# MOASCT.net
KiCad netlist of a schematic drawn in Altium Designer
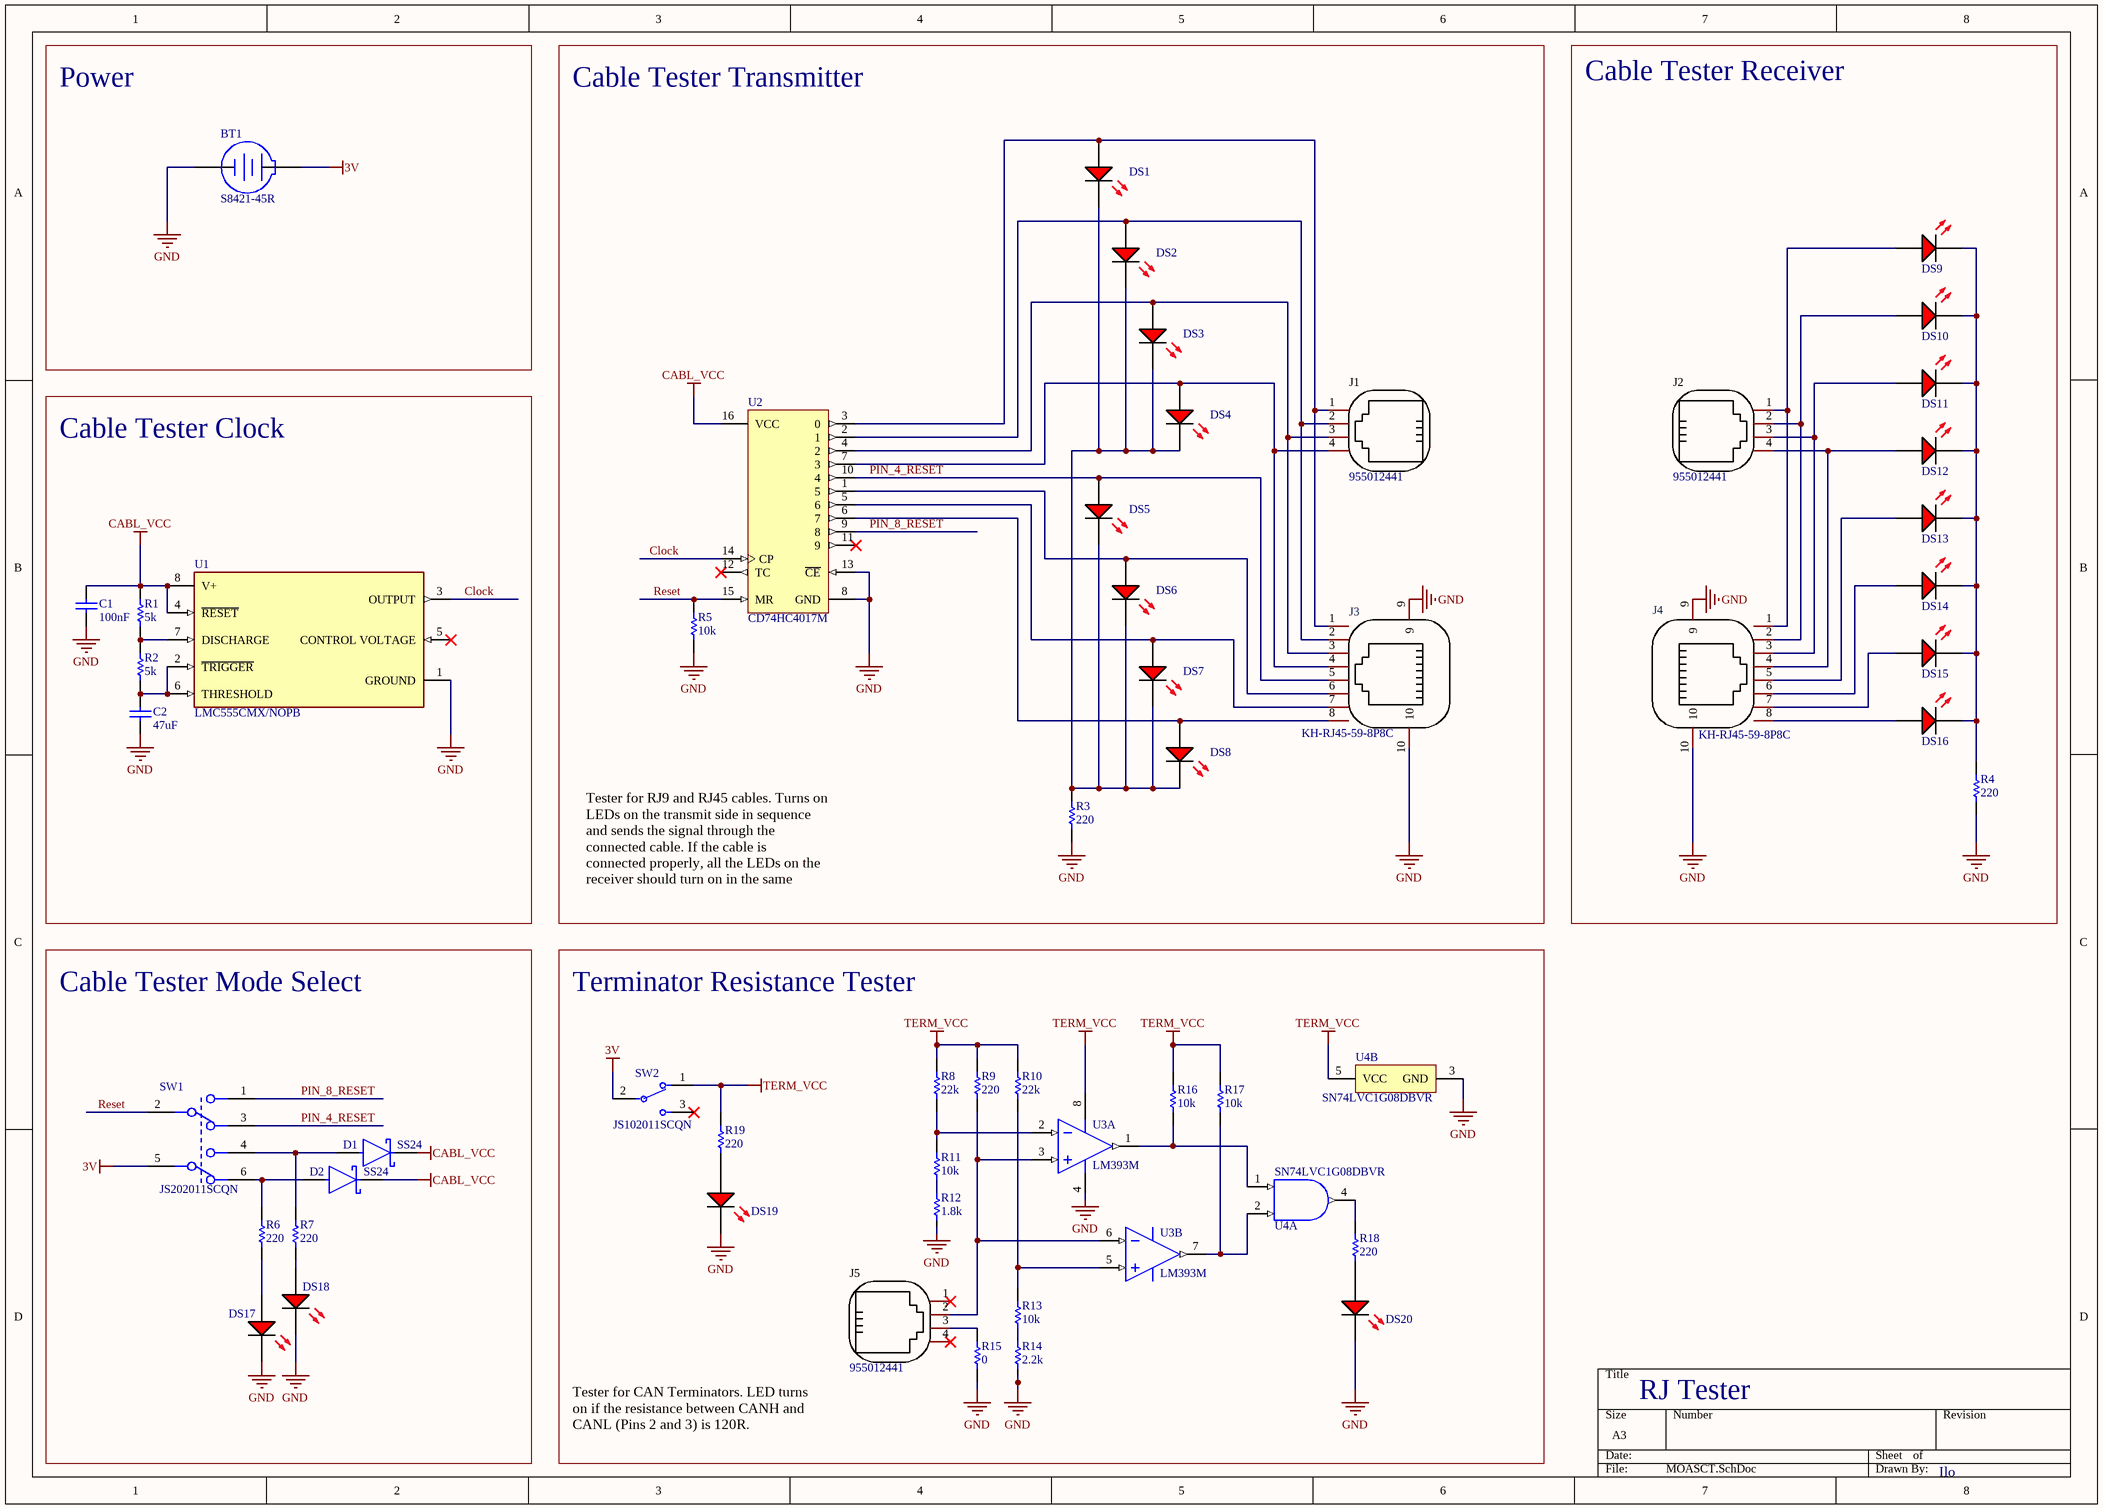
[diagram p0: MOASCT.SchDoc]

(export (version "E")
  (design (tool "Eeschema 10.0.6"))
  (components
    (comp (ref "BT1")
      (value "S8421-45R")
      (footprint "HRWN-S8421-45R_V")
      (description "Bettery Coin Cell Holder, Suitable for CR2032, -40 to 105 degC, 2-Pin SMD, RoHS, Tape and Reel")
      (fields (field (name "MANUFACTURER") "Harwin"))
      (libsource (lib "Altium Content Vault") (part "BATTERY-HOLDER-COIN-2"))
    )
    (comp (ref "C1")
      (value "100nF")
      (footprint "CAPC1608X92X38ML15T08")
      (fields (field (name "MANUFACTURER") "Vitramon") (field (name "PART NUMBER") "VJ0603Y103KXAAC"))
      (libsource (lib "Altium Content Vault") (part "CAP"))
    )
    (comp (ref "C2")
      (value "47uF")
      (footprint "CAPC2013X145X48NL20T23")
      (fields (field (name "PART NUMBER") "VJ0805Y104KXAAT") (field (name "MANUFACTURER") "Vitramon"))
      (libsource (lib "Altium Content Vault") (part "CAP"))
    )
    (comp (ref "D1")
      (value "SS24")
      (footprint "FP-95401-MFG")
      (description "SS24-E3/5BT Rectifier Diode, Schottky, 1 Phase, 1 Element, 2A, 40V V(RRM), Silicon, DO-214AA")
      (libsource (lib "Altium Content Vault") (part "c1678fac7984e62e0809fbf79c06691"))
    )
    (comp (ref "D2")
      (value "SS24")
      (footprint "FP-95401-MFG")
      (description "SS24-E3/5BT Rectifier Diode, Schottky, 1 Phase, 1 Element, 2A, 40V V(RRM), Silicon, DO-214AA")
      (libsource (lib "Altium Content Vault") (part "c1678fac7984e62e0809fbf79c06691"))
    )
    (comp (ref "DS1")
      (value "SML-LXT0805IW-TR")
      (footprint "LUMX-SML-LXT0805_V")
      (description "LED, RED, 635 nm, 2 V, -25 to 80 degC, 2-Pin SMD, RoHS, Tape and Reel")
      (libsource (lib "Altium Content Vault") (part "LED-RED-AK-2"))
    )
    (comp (ref "DS2")
      (value "SML-LXT0805IW-TR")
      (footprint "LUMX-SML-LXT0805_V")
      (description "LED, RED, 635 nm, 2 V, -25 to 80 degC, 2-Pin SMD, RoHS, Tape and Reel")
      (libsource (lib "Altium Content Vault") (part "LED-RED-AK-2"))
    )
    (comp (ref "DS3")
      (value "SML-LXT0805IW-TR")
      (footprint "LUMX-SML-LXT0805_V")
      (description "LED, RED, 635 nm, 2 V, -25 to 80 degC, 2-Pin SMD, RoHS, Tape and Reel")
      (libsource (lib "Altium Content Vault") (part "LED-RED-AK-2"))
    )
    (comp (ref "DS4")
      (value "SML-LXT0805IW-TR")
      (footprint "LUMX-SML-LXT0805_V")
      (description "LED, RED, 635 nm, 2 V, -25 to 80 degC, 2-Pin SMD, RoHS, Tape and Reel")
      (libsource (lib "Altium Content Vault") (part "LED-RED-AK-2"))
    )
    (comp (ref "DS5")
      (value "SML-LXT0805IW-TR")
      (footprint "LUMX-SML-LXT0805_V")
      (description "LED, RED, 635 nm, 2 V, -25 to 80 degC, 2-Pin SMD, RoHS, Tape and Reel")
      (libsource (lib "Altium Content Vault") (part "LED-RED-AK-2"))
    )
    (comp (ref "DS6")
      (value "SML-LXT0805IW-TR")
      (footprint "LUMX-SML-LXT0805_V")
      (description "LED, RED, 635 nm, 2 V, -25 to 80 degC, 2-Pin SMD, RoHS, Tape and Reel")
      (libsource (lib "Altium Content Vault") (part "LED-RED-AK-2"))
    )
    (comp (ref "DS7")
      (value "SML-LXT0805IW-TR")
      (footprint "LUMX-SML-LXT0805_V")
      (description "LED, RED, 635 nm, 2 V, -25 to 80 degC, 2-Pin SMD, RoHS, Tape and Reel")
      (libsource (lib "Altium Content Vault") (part "LED-RED-AK-2"))
    )
    (comp (ref "DS8")
      (value "SML-LXT0805IW-TR")
      (footprint "LUMX-SML-LXT0805_V")
      (description "LED, RED, 635 nm, 2 V, -25 to 80 degC, 2-Pin SMD, RoHS, Tape and Reel")
      (libsource (lib "Altium Content Vault") (part "LED-RED-AK-2"))
    )
    (comp (ref "DS9")
      (value "SML-LXT0805IW-TR")
      (footprint "LUMX-SML-LXT0805_V")
      (description "LED, RED, 635 nm, 2 V, -25 to 80 degC, 2-Pin SMD, RoHS, Tape and Reel")
      (libsource (lib "Altium Content Vault") (part "LED-RED-AK-2"))
    )
    (comp (ref "DS10")
      (value "SML-LXT0805IW-TR")
      (footprint "LUMX-SML-LXT0805_V")
      (description "LED, RED, 635 nm, 2 V, -25 to 80 degC, 2-Pin SMD, RoHS, Tape and Reel")
      (libsource (lib "Altium Content Vault") (part "LED-RED-AK-2"))
    )
    (comp (ref "DS11")
      (value "SML-LXT0805IW-TR")
      (footprint "LUMX-SML-LXT0805_V")
      (description "LED, RED, 635 nm, 2 V, -25 to 80 degC, 2-Pin SMD, RoHS, Tape and Reel")
      (libsource (lib "Altium Content Vault") (part "LED-RED-AK-2"))
    )
    (comp (ref "DS12")
      (value "SML-LXT0805IW-TR")
      (footprint "LUMX-SML-LXT0805_V")
      (description "LED, RED, 635 nm, 2 V, -25 to 80 degC, 2-Pin SMD, RoHS, Tape and Reel")
      (libsource (lib "Altium Content Vault") (part "LED-RED-AK-2"))
    )
    (comp (ref "DS13")
      (value "SML-LXT0805IW-TR")
      (footprint "LUMX-SML-LXT0805_V")
      (description "LED, RED, 635 nm, 2 V, -25 to 80 degC, 2-Pin SMD, RoHS, Tape and Reel")
      (libsource (lib "Altium Content Vault") (part "LED-RED-AK-2"))
    )
    (comp (ref "DS14")
      (value "SML-LXT0805IW-TR")
      (footprint "LUMX-SML-LXT0805_V")
      (description "LED, RED, 635 nm, 2 V, -25 to 80 degC, 2-Pin SMD, RoHS, Tape and Reel")
      (libsource (lib "Altium Content Vault") (part "LED-RED-AK-2"))
    )
    (comp (ref "DS15")
      (value "SML-LXT0805IW-TR")
      (footprint "LUMX-SML-LXT0805_V")
      (description "LED, RED, 635 nm, 2 V, -25 to 80 degC, 2-Pin SMD, RoHS, Tape and Reel")
      (libsource (lib "Altium Content Vault") (part "LED-RED-AK-2"))
    )
    (comp (ref "DS16")
      (value "SML-LXT0805IW-TR")
      (footprint "LUMX-SML-LXT0805_V")
      (description "LED, RED, 635 nm, 2 V, -25 to 80 degC, 2-Pin SMD, RoHS, Tape and Reel")
      (libsource (lib "Altium Content Vault") (part "LED-RED-AK-2"))
    )
    (comp (ref "DS17")
      (value "SML-LXT0805IW-TR")
      (footprint "LUMX-SML-LXT0805_V")
      (description "LED, RED, 635 nm, 2 V, -25 to 80 degC, 2-Pin SMD, RoHS, Tape and Reel")
      (libsource (lib "Altium Content Vault") (part "LED-RED-AK-2"))
    )
    (comp (ref "DS18")
      (value "SML-LXT0805IW-TR")
      (footprint "LUMX-SML-LXT0805_V")
      (description "LED, RED, 635 nm, 2 V, -25 to 80 degC, 2-Pin SMD, RoHS, Tape and Reel")
      (libsource (lib "Altium Content Vault") (part "LED-RED-AK-2"))
    )
    (comp (ref "DS19")
      (value "SML-LXT0805IW-TR")
      (footprint "LUMX-SML-LXT0805_V")
      (description "LED, RED, 635 nm, 2 V, -25 to 80 degC, 2-Pin SMD, RoHS, Tape and Reel")
      (libsource (lib "Altium Content Vault") (part "LED-RED-AK-2"))
    )
    (comp (ref "DS20")
      (value "SML-LXT0805IW-TR")
      (footprint "LUMX-SML-LXT0805_V")
      (description "LED, RED, 635 nm, 2 V, -25 to 80 degC, 2-Pin SMD, RoHS, Tape and Reel")
      (libsource (lib "Altium Content Vault") (part "LED-RED-AK-2"))
    )
    (comp (ref "J1")
      (value "955012441")
      (footprint "RJ45-TH_95501-2441:RJ45-TH_95501-2441")
      (fields (field (name "MANUFACTURER") "MOLEX"))
      (libsource (lib "9550124411_955012441.schdoc") (part "955012441"))
    )
    (comp (ref "J2")
      (value "955012441")
      (footprint "RJ45-TH_95501-2441:RJ45-TH_95501-2441")
      (fields (field (name "MANUFACTURER") "MOLEX"))
      (libsource (lib "9550124411_955012441.schdoc") (part "955012441"))
    )
    (comp (ref "J3")
      (value "KH-RJ45-59-8P8C")
      (footprint "RJ45-TH_KINGHELM_KH-RJ45-59-8P8C:RJ45-TH_KINGHELM_KH-RJ45-59-8P8C")
      (fields (field (name "MANUFACTURER") "kinghelm(金航标)"))
      (libsource (lib "KH-RJ45-59-8P8C1_KH-RJ45-59-8P8C") (part "KH-RJ45-59-8P8C"))
    )
    (comp (ref "J4")
      (value "KH-RJ45-59-8P8C")
      (footprint "RJ45-TH_KINGHELM_KH-RJ45-59-8P8C:RJ45-TH_KINGHELM_KH-RJ45-59-8P8C")
      (fields (field (name "MANUFACTURER") "kinghelm(金航标)"))
      (libsource (lib "KH-RJ45-59-8P8C1_KH-RJ45-59-8P8C") (part "KH-RJ45-59-8P8C"))
    )
    (comp (ref "J5")
      (value "955012441")
      (footprint "RJ45-TH_95501-2441:RJ45-TH_95501-2441")
      (fields (field (name "MANUFACTURER") "MOLEX"))
      (libsource (lib "9550124411_955012441.schdoc") (part "955012441"))
    )
    (comp (ref "R1")
      (value "5k")
      (footprint "RESC1609X50X30ML10T20")
      (fields (field (name "PART NUMBER") "CRCW060315K0FKEA") (field (name "MANUFACTURER") "Vishay Dale"))
      (libsource (lib "Altium Content Vault") (part "RES"))
    )
    (comp (ref "R2")
      (value "5k")
      (footprint "RESC1609X50X30ML10T20")
      (fields (field (name "PART NUMBER") "CRCW060315K0FKEA") (field (name "MANUFACTURER") "Vishay Dale"))
      (libsource (lib "Altium Content Vault") (part "RES"))
    )
    (comp (ref "R3")
      (value "220")
      (footprint "RESC1609X50X30ML10T20")
      (fields (field (name "PART NUMBER") "CRCW060315K0FKEA") (field (name "MANUFACTURER") "Vishay Dale"))
      (libsource (lib "Altium Content Vault") (part "RES"))
    )
    (comp (ref "R4")
      (value "220")
      (footprint "RESC1609X50X30ML10T20")
      (fields (field (name "PART NUMBER") "CRCW060315K0FKEA") (field (name "MANUFACTURER") "Vishay Dale"))
      (libsource (lib "Altium Content Vault") (part "RES"))
    )
    (comp (ref "R5")
      (value "10k")
      (footprint "RESC1609X50X30ML10T20")
      (fields (field (name "PART NUMBER") "CRCW060315K0FKEA") (field (name "MANUFACTURER") "Vishay Dale"))
      (libsource (lib "Altium Content Vault") (part "RES"))
    )
    (comp (ref "R6")
      (value "220")
      (footprint "RESC1609X50X30ML10T20")
      (fields (field (name "PART NUMBER") "CRCW060315K0FKEA") (field (name "MANUFACTURER") "Vishay Dale"))
      (libsource (lib "Altium Content Vault") (part "RES"))
    )
    (comp (ref "R7")
      (value "220")
      (footprint "RESC1609X50X30ML10T20")
      (fields (field (name "PART NUMBER") "CRCW060315K0FKEA") (field (name "MANUFACTURER") "Vishay Dale"))
      (libsource (lib "Altium Content Vault") (part "RES"))
    )
    (comp (ref "R8")
      (value "22k")
      (footprint "RESC1609X50X30ML10T20")
      (fields (field (name "PART NUMBER") "CRCW060315K0FKEA") (field (name "MANUFACTURER") "Vishay Dale"))
      (libsource (lib "Altium Content Vault") (part "RES"))
    )
    (comp (ref "R9")
      (value "220")
      (footprint "RESC1609X50X30ML10T20")
      (fields (field (name "PART NUMBER") "CRCW060315K0FKEA") (field (name "MANUFACTURER") "Vishay Dale"))
      (libsource (lib "Altium Content Vault") (part "RES"))
    )
    (comp (ref "R10")
      (value "22k")
      (footprint "RESC1609X50X30ML10T20")
      (fields (field (name "PART NUMBER") "CRCW060315K0FKEA") (field (name "MANUFACTURER") "Vishay Dale"))
      (libsource (lib "Altium Content Vault") (part "RES"))
    )
    (comp (ref "R11")
      (value "10k")
      (footprint "RESC1609X50X30ML10T20")
      (fields (field (name "PART NUMBER") "CRCW060315K0FKEA") (field (name "MANUFACTURER") "Vishay Dale"))
      (libsource (lib "Altium Content Vault") (part "RES"))
    )
    (comp (ref "R12")
      (value "1.8k")
      (footprint "RESC1609X50X30ML10T20")
      (fields (field (name "PART NUMBER") "CRCW060315K0FKEA") (field (name "MANUFACTURER") "Vishay Dale"))
      (libsource (lib "Altium Content Vault") (part "RES"))
    )
    (comp (ref "R13")
      (value "10k")
      (footprint "RESC1609X50X30ML10T20")
      (fields (field (name "PART NUMBER") "CRCW060315K0FKEA") (field (name "MANUFACTURER") "Vishay Dale"))
      (libsource (lib "Altium Content Vault") (part "RES"))
    )
    (comp (ref "R14")
      (value "2.2k")
      (footprint "RESC1609X50X30ML10T20")
      (fields (field (name "PART NUMBER") "CRCW060315K0FKEA") (field (name "MANUFACTURER") "Vishay Dale"))
      (libsource (lib "Altium Content Vault") (part "RES"))
    )
    (comp (ref "R15")
      (value "0")
      (footprint "RESC1609X50X30ML10T20")
      (fields (field (name "PART NUMBER") "CRCW060315K0FKEA") (field (name "MANUFACTURER") "Vishay Dale"))
      (libsource (lib "Altium Content Vault") (part "RES"))
    )
    (comp (ref "R16")
      (value "10k")
      (footprint "RESC1609X50X30ML10T20")
      (fields (field (name "PART NUMBER") "CRCW060315K0FKEA") (field (name "MANUFACTURER") "Vishay Dale"))
      (libsource (lib "Altium Content Vault") (part "RES"))
    )
    (comp (ref "R17")
      (value "10k")
      (footprint "RESC1609X50X30ML10T20")
      (fields (field (name "PART NUMBER") "CRCW060315K0FKEA") (field (name "MANUFACTURER") "Vishay Dale"))
      (libsource (lib "Altium Content Vault") (part "RES"))
    )
    (comp (ref "R18")
      (value "220")
      (footprint "RESC1609X50X30ML10T20")
      (fields (field (name "PART NUMBER") "CRCW060315K0FKEA") (field (name "MANUFACTURER") "Vishay Dale"))
      (libsource (lib "Altium Content Vault") (part "RES"))
    )
    (comp (ref "R19")
      (value "220")
      (footprint "RESC1609X50X30ML10T20")
      (fields (field (name "PART NUMBER") "CRCW060315K0FKEA") (field (name "MANUFACTURER") "Vishay Dale"))
      (libsource (lib "Altium Content Vault") (part "RES"))
    )
    (comp (ref "SW1")
      (value "JS202011SCQN")
      (footprint "FP-JS202011SCQN-MFG")
      (description "SWITCH SLIDE DPDT 300MA 6V")
      (libsource (lib "Altium Content Vault") (part "ac99ea1af431c19115f5225061c5c88"))
    )
    (comp (ref "SW2")
      (value "JS102011SCQN")
      (footprint "FP-JS102011SCQN-MFG")
      (description "SWITCH SLIDE SPDT 300MA 6V")
      (libsource (lib "Altium Content Vault") (part "39e195cbbadc85d1df0d7eb6847d379"))
    )
    (comp (ref "U1")
      (value "LMC555CMX/NOPB")
      (footprint "FP-D0008A-MFG")
      (description "IC OSC SINGLE TIMER 3MHZ 8-SOIC")
      (fields
        (field (name "OCTOPART") "https://octopart.com/lmc555cmx%2Fnopb-texas+instruments-24815227")
        (field (name "MANUFACTURER") "Texas Instruments")
      )
      (libsource (lib "Altium Content Vault") (part "2d4910f0af3888ed72da4973d42bf58"))
    )
    (comp (ref "U2")
      (value "CD74HC4017M")
      (footprint "D0016A_N")
      (description "High Speed CMOS Logic Decade Counter/Divider with 10 Decoded Outputs, D0016A, TUBE")
      (fields
        (field (name "MANUFACTURER") "Texas Instruments")
        (field (name "GENERIC PART NUMBER") "CD74HC4017")
      )
      (libsource (lib "Altium Content Vault") (part "TI-CD74HC4017-16"))
    )
    (comp (ref "U3")
      (value "LM393M")
      (footprint "D0008A_L")
      (description "Low Power Low Offset Voltage Dual Comparator, 8-pin Narrow SOIC")
      (fields (field (name "MANUFACTURER") "Texas Instruments"))
      (libsource (lib "Altium Content Vault") (part "AN-COMP-LM193-8"))
    )
    (comp (ref "U4")
      (value "SN74LVC1G08DBVR")
      (footprint "DBV0005A_M")
      (description "Single 2-Input Positive-AND Gate, DBV0005A, LARGE T&R")
      (fields
        (field (name "GENERIC PART NUMBER") "SN74LVC1G08")
        (field (name "MANUFACTURER") "Texas Instruments")
      )
      (libsource (lib "Altium Content Vault") (part "TI-SN74XXX1X08-5"))
    )
  )
  (nets
    (net (code "1") (name "/Clock") (class "Default")
      (node (ref "U1") (pin "3") (pinfunction "OUTPUT_3") (pintype "output"))
      (node (ref "U2") (pin "14") (pinfunction "CP_14") (pintype "input"))
    )
    (net (code "2") (name "/PIN_4_RESET") (class "Default")
      (node (ref "DS5") (pin "1") (pinfunction "A_1") (pintype "passive"))
      (node (ref "J3") (pin "5") (pinfunction "5_5") (pintype "passive"))
      (node (ref "SW1") (pin "3") (pinfunction "3_3") (pintype "passive"))
      (node (ref "U2") (pin "10") (pinfunction "4_10") (pintype "output"))
    )
    (net (code "3") (name "/PIN_8_RESET") (class "Default")
      (node (ref "SW1") (pin "1") (pinfunction "1_1") (pintype "passive"))
      (node (ref "U2") (pin "9") (pinfunction "8_9") (pintype "output"))
    )
    (net (code "4") (name "/Reset") (class "Default")
      (node (ref "R5") (pin "2") (pinfunction "2_2") (pintype "passive"))
      (node (ref "SW1") (pin "2") (pinfunction "2_2") (pintype "passive"))
      (node (ref "U2") (pin "15") (pinfunction "MR_15") (pintype "input"))
    )
    (net (code "5") (name "3V") (class "Default")
      (node (ref "BT1") (pin "1") (pinfunction "+_1") (pintype "passive"))
      (node (ref "SW1") (pin "5") (pinfunction "5_5") (pintype "passive"))
      (node (ref "SW2") (pin "2") (pinfunction "C_2") (pintype "passive"))
    )
    (net (code "6") (name "CABL_VCC") (class "Default")
      (node (ref "C1") (pin "2") (pinfunction "2_2") (pintype "passive"))
      (node (ref "D1") (pin "1") (pinfunction "C_1") (pintype "passive"))
      (node (ref "D2") (pin "1") (pinfunction "C_1") (pintype "passive"))
      (node (ref "R1") (pin "2") (pinfunction "2_2") (pintype "passive"))
      (node (ref "U1") (pin "4") (pinfunction "~{RESET}_4") (pintype "input"))
      (node (ref "U1") (pin "8") (pinfunction "V+_8") (pintype "power_in"))
      (node (ref "U2") (pin "16") (pinfunction "VCC_16") (pintype "power_in"))
    )
    (net (code "7") (name "GND") (class "Default")
      (node (ref "BT1") (pin "2") (pinfunction "-_2") (pintype "passive"))
      (node (ref "C1") (pin "1") (pinfunction "1_1") (pintype "passive"))
      (node (ref "C2") (pin "2") (pinfunction "2_2") (pintype "passive"))
      (node (ref "DS17") (pin "2") (pinfunction "K_2") (pintype "passive"))
      (node (ref "DS18") (pin "2") (pinfunction "K_2") (pintype "passive"))
      (node (ref "DS19") (pin "2") (pinfunction "K_2") (pintype "passive"))
      (node (ref "DS20") (pin "2") (pinfunction "K_2") (pintype "passive"))
      (node (ref "J3") (pin "10") (pinfunction "10_10") (pintype "passive"))
      (node (ref "J3") (pin "9") (pinfunction "9_9") (pintype "passive"))
      (node (ref "J4") (pin "10") (pinfunction "10_10") (pintype "passive"))
      (node (ref "J4") (pin "9") (pinfunction "9_9") (pintype "passive"))
      (node (ref "R12") (pin "1") (pinfunction "1_1") (pintype "passive"))
      (node (ref "R14") (pin "1") (pinfunction "1_1") (pintype "passive"))
      (node (ref "R15") (pin "1") (pinfunction "1_1") (pintype "passive"))
      (node (ref "R3") (pin "1") (pinfunction "1_1") (pintype "passive"))
      (node (ref "R4") (pin "1") (pinfunction "1_1") (pintype "passive"))
      (node (ref "R5") (pin "1") (pinfunction "1_1") (pintype "passive"))
      (node (ref "U1") (pin "1") (pinfunction "GROUND_1") (pintype "power_in"))
      (node (ref "U2") (pin "13") (pinfunction "~{CE}_13") (pintype "input"))
      (node (ref "U2") (pin "8") (pinfunction "GND_8") (pintype "power_in"))
      (node (ref "U3") (pin "4") (pinfunction "GND_4") (pintype "power_in"))
      (node (ref "U4") (pin "3") (pinfunction "GND_3") (pintype "power_in"))
    )
    (net (code "8") (name "Net-(D1-A)") (class "Default")
      (node (ref "D1") (pin "2") (pinfunction "A_2") (pintype "passive"))
      (node (ref "R7") (pin "2") (pinfunction "2_2") (pintype "passive"))
      (node (ref "SW1") (pin "4") (pinfunction "4_4") (pintype "passive"))
    )
    (net (code "9") (name "Net-(D2-A)") (class "Default")
      (node (ref "D2") (pin "2") (pinfunction "A_2") (pintype "passive"))
      (node (ref "R6") (pin "2") (pinfunction "2_2") (pintype "passive"))
      (node (ref "SW1") (pin "6") (pinfunction "6_6") (pintype "passive"))
    )
    (net (code "10") (name "Net-(DS1-A)") (class "Default")
      (node (ref "DS1") (pin "1") (pinfunction "A_1") (pintype "passive"))
      (node (ref "J1") (pin "1") (pinfunction "1_1") (pintype "passive"))
      (node (ref "J3") (pin "1") (pinfunction "1_1") (pintype "passive"))
      (node (ref "U2") (pin "3") (pinfunction "0_3") (pintype "output"))
    )
    (net (code "11") (name "Net-(DS1-K)") (class "Default")
      (node (ref "DS1") (pin "2") (pinfunction "K_2") (pintype "passive"))
      (node (ref "DS2") (pin "2") (pinfunction "K_2") (pintype "passive"))
      (node (ref "DS3") (pin "2") (pinfunction "K_2") (pintype "passive"))
      (node (ref "DS4") (pin "2") (pinfunction "K_2") (pintype "passive"))
      (node (ref "DS5") (pin "2") (pinfunction "K_2") (pintype "passive"))
      (node (ref "DS6") (pin "2") (pinfunction "K_2") (pintype "passive"))
      (node (ref "DS7") (pin "2") (pinfunction "K_2") (pintype "passive"))
      (node (ref "DS8") (pin "2") (pinfunction "K_2") (pintype "passive"))
      (node (ref "R3") (pin "2") (pinfunction "2_2") (pintype "passive"))
    )
    (net (code "12") (name "Net-(DS2-A)") (class "Default")
      (node (ref "DS2") (pin "1") (pinfunction "A_1") (pintype "passive"))
      (node (ref "J1") (pin "2") (pinfunction "2_2") (pintype "passive"))
      (node (ref "J3") (pin "2") (pinfunction "2_2") (pintype "passive"))
      (node (ref "U2") (pin "2") (pinfunction "1_2") (pintype "output"))
    )
    (net (code "13") (name "Net-(DS3-A)") (class "Default")
      (node (ref "DS3") (pin "1") (pinfunction "A_1") (pintype "passive"))
      (node (ref "J1") (pin "3") (pinfunction "3_3") (pintype "passive"))
      (node (ref "J3") (pin "3") (pinfunction "3_3") (pintype "passive"))
      (node (ref "U2") (pin "4") (pinfunction "2_4") (pintype "output"))
    )
    (net (code "14") (name "Net-(DS4-A)") (class "Default")
      (node (ref "DS4") (pin "1") (pinfunction "A_1") (pintype "passive"))
      (node (ref "J1") (pin "4") (pinfunction "4_4") (pintype "passive"))
      (node (ref "J3") (pin "4") (pinfunction "4_4") (pintype "passive"))
      (node (ref "U2") (pin "7") (pinfunction "3_7") (pintype "output"))
    )
    (net (code "15") (name "Net-(DS6-A)") (class "Default")
      (node (ref "DS6") (pin "1") (pinfunction "A_1") (pintype "passive"))
      (node (ref "J3") (pin "6") (pinfunction "6_6") (pintype "passive"))
      (node (ref "U2") (pin "1") (pinfunction "5_1") (pintype "output"))
    )
    (net (code "16") (name "Net-(DS7-A)") (class "Default")
      (node (ref "DS7") (pin "1") (pinfunction "A_1") (pintype "passive"))
      (node (ref "J3") (pin "7") (pinfunction "7_7") (pintype "passive"))
      (node (ref "U2") (pin "5") (pinfunction "6_5") (pintype "output"))
    )
    (net (code "17") (name "Net-(DS8-A)") (class "Default")
      (node (ref "DS8") (pin "1") (pinfunction "A_1") (pintype "passive"))
      (node (ref "J3") (pin "8") (pinfunction "8_8") (pintype "passive"))
      (node (ref "U2") (pin "6") (pinfunction "7_6") (pintype "output"))
    )
    (net (code "18") (name "Net-(DS9-A)") (class "Default")
      (node (ref "DS9") (pin "1") (pinfunction "A_1") (pintype "passive"))
      (node (ref "J2") (pin "1") (pinfunction "1_1") (pintype "passive"))
      (node (ref "J4") (pin "1") (pinfunction "1_1") (pintype "passive"))
    )
    (net (code "19") (name "Net-(DS10-A)") (class "Default")
      (node (ref "DS10") (pin "1") (pinfunction "A_1") (pintype "passive"))
      (node (ref "J2") (pin "2") (pinfunction "2_2") (pintype "passive"))
      (node (ref "J4") (pin "2") (pinfunction "2_2") (pintype "passive"))
    )
    (net (code "20") (name "Net-(DS10-K)") (class "Default")
      (node (ref "DS10") (pin "2") (pinfunction "K_2") (pintype "passive"))
      (node (ref "DS11") (pin "2") (pinfunction "K_2") (pintype "passive"))
      (node (ref "DS12") (pin "2") (pinfunction "K_2") (pintype "passive"))
      (node (ref "DS13") (pin "2") (pinfunction "K_2") (pintype "passive"))
      (node (ref "DS14") (pin "2") (pinfunction "K_2") (pintype "passive"))
      (node (ref "DS15") (pin "2") (pinfunction "K_2") (pintype "passive"))
      (node (ref "DS16") (pin "2") (pinfunction "K_2") (pintype "passive"))
      (node (ref "DS9") (pin "2") (pinfunction "K_2") (pintype "passive"))
      (node (ref "R4") (pin "2") (pinfunction "2_2") (pintype "passive"))
    )
    (net (code "21") (name "Net-(DS11-A)") (class "Default")
      (node (ref "DS11") (pin "1") (pinfunction "A_1") (pintype "passive"))
      (node (ref "J2") (pin "3") (pinfunction "3_3") (pintype "passive"))
      (node (ref "J4") (pin "3") (pinfunction "3_3") (pintype "passive"))
    )
    (net (code "22") (name "Net-(DS12-A)") (class "Default")
      (node (ref "DS12") (pin "1") (pinfunction "A_1") (pintype "passive"))
      (node (ref "J2") (pin "4") (pinfunction "4_4") (pintype "passive"))
      (node (ref "J4") (pin "4") (pinfunction "4_4") (pintype "passive"))
    )
    (net (code "23") (name "Net-(DS13-A)") (class "Default")
      (node (ref "DS13") (pin "1") (pinfunction "A_1") (pintype "passive"))
      (node (ref "J4") (pin "5") (pinfunction "5_5") (pintype "passive"))
    )
    (net (code "24") (name "Net-(DS14-A)") (class "Default")
      (node (ref "DS14") (pin "1") (pinfunction "A_1") (pintype "passive"))
      (node (ref "J4") (pin "6") (pinfunction "6_6") (pintype "passive"))
    )
    (net (code "25") (name "Net-(DS15-A)") (class "Default")
      (node (ref "DS15") (pin "1") (pinfunction "A_1") (pintype "passive"))
      (node (ref "J4") (pin "7") (pinfunction "7_7") (pintype "passive"))
    )
    (net (code "26") (name "Net-(DS16-A)") (class "Default")
      (node (ref "DS16") (pin "1") (pinfunction "A_1") (pintype "passive"))
      (node (ref "J4") (pin "8") (pinfunction "8_8") (pintype "passive"))
    )
    (net (code "27") (name "Net-(DS17-A)") (class "Default")
      (node (ref "DS17") (pin "1") (pinfunction "A_1") (pintype "passive"))
      (node (ref "R6") (pin "1") (pinfunction "1_1") (pintype "passive"))
    )
    (net (code "28") (name "Net-(DS18-A)") (class "Default")
      (node (ref "DS18") (pin "1") (pinfunction "A_1") (pintype "passive"))
      (node (ref "R7") (pin "1") (pinfunction "1_1") (pintype "passive"))
    )
    (net (code "29") (name "Net-(DS19-A)") (class "Default")
      (node (ref "DS19") (pin "1") (pinfunction "A_1") (pintype "passive"))
      (node (ref "R19") (pin "1") (pinfunction "1_1") (pintype "passive"))
    )
    (net (code "30") (name "Net-(DS20-A)") (class "Default")
      (node (ref "DS20") (pin "1") (pinfunction "A_1") (pintype "passive"))
      (node (ref "R18") (pin "1") (pinfunction "1_1") (pintype "passive"))
    )
    (net (code "31") (name "Net-(J5-Pad3)") (class "Default")
      (node (ref "J5") (pin "3") (pinfunction "3_3") (pintype "passive"))
      (node (ref "R15") (pin "2") (pinfunction "2_2") (pintype "passive"))
    )
    (net (code "32") (name "Net-(R11-Pad1)") (class "Default")
      (node (ref "R11") (pin "1") (pinfunction "1_1") (pintype "passive"))
      (node (ref "R12") (pin "2") (pinfunction "2_2") (pintype "passive"))
    )
    (net (code "33") (name "Net-(R13-Pad1)") (class "Default")
      (node (ref "R13") (pin "1") (pinfunction "1_1") (pintype "passive"))
      (node (ref "R14") (pin "2") (pinfunction "2_2") (pintype "passive"))
    )
    (net (code "34") (name "Net-(U1-DISCHARGE)") (class "Default")
      (node (ref "R1") (pin "1") (pinfunction "1_1") (pintype "passive"))
      (node (ref "R2") (pin "2") (pinfunction "2_2") (pintype "passive"))
      (node (ref "U1") (pin "7") (pinfunction "DISCHARGE_7") (pintype "input"))
    )
    (net (code "35") (name "Net-(U1-THRESHOLD)") (class "Default")
      (node (ref "C2") (pin "1") (pinfunction "1_1") (pintype "passive"))
      (node (ref "R2") (pin "1") (pinfunction "1_1") (pintype "passive"))
      (node (ref "U1") (pin "2") (pinfunction "~{TRIGGER}_2") (pintype "input"))
      (node (ref "U1") (pin "6") (pinfunction "THRESHOLD_6") (pintype "input"))
    )
    (net (code "36") (name "Net-(U3A-INA+)") (class "Default")
      (node (ref "J5") (pin "2") (pinfunction "2_2") (pintype "passive"))
      (node (ref "R9") (pin "1") (pinfunction "1_1") (pintype "passive"))
      (node (ref "U3") (pin "3") (pinfunction "INA+_3") (pintype "input"))
      (node (ref "U3") (pin "6") (pinfunction "INB-_6") (pintype "input"))
    )
    (net (code "37") (name "Net-(U3A-INA-)") (class "Default")
      (node (ref "R11") (pin "2") (pinfunction "2_2") (pintype "passive"))
      (node (ref "R8") (pin "1") (pinfunction "1_1") (pintype "passive"))
      (node (ref "U3") (pin "2") (pinfunction "INA-_2") (pintype "input"))
    )
    (net (code "38") (name "Net-(U3A-OUTA)") (class "Default")
      (node (ref "R16") (pin "1") (pinfunction "1_1") (pintype "passive"))
      (node (ref "U3") (pin "1") (pinfunction "OUTA_1") (pintype "output"))
      (node (ref "U4") (pin "1") (pinfunction "A_1") (pintype "input"))
    )
    (net (code "39") (name "Net-(U3B-INB+)") (class "Default")
      (node (ref "R10") (pin "1") (pinfunction "1_1") (pintype "passive"))
      (node (ref "R13") (pin "2") (pinfunction "2_2") (pintype "passive"))
      (node (ref "U3") (pin "5") (pinfunction "INB+_5") (pintype "input"))
    )
    (net (code "40") (name "Net-(U3B-OUTB)") (class "Default")
      (node (ref "R17") (pin "1") (pinfunction "1_1") (pintype "passive"))
      (node (ref "U3") (pin "7") (pinfunction "OUTB_7") (pintype "output"))
      (node (ref "U4") (pin "2") (pinfunction "B_2") (pintype "input"))
    )
    (net (code "41") (name "Net-(U4A-Y)") (class "Default")
      (node (ref "R18") (pin "2") (pinfunction "2_2") (pintype "passive"))
      (node (ref "U4") (pin "4") (pinfunction "Y_4") (pintype "output"))
    )
    (net (code "42") (name "TERM_VCC") (class "Default")
      (node (ref "R10") (pin "2") (pinfunction "2_2") (pintype "passive"))
      (node (ref "R16") (pin "2") (pinfunction "2_2") (pintype "passive"))
      (node (ref "R17") (pin "2") (pinfunction "2_2") (pintype "passive"))
      (node (ref "R19") (pin "2") (pinfunction "2_2") (pintype "passive"))
      (node (ref "R8") (pin "2") (pinfunction "2_2") (pintype "passive"))
      (node (ref "R9") (pin "2") (pinfunction "2_2") (pintype "passive"))
      (node (ref "SW2") (pin "1") (pinfunction "1_1") (pintype "passive"))
      (node (ref "U3") (pin "8") (pinfunction "V+_8") (pintype "power_in"))
      (node (ref "U4") (pin "5") (pinfunction "VCC_5") (pintype "power_in"))
    )
    (net (code "43") (name "unconnected-(J5-Pad1)") (class "Default")
      (node (ref "J5") (pin "1") (pinfunction "1_1") (pintype "passive+no_connect"))
    )
    (net (code "44") (name "unconnected-(J5-Pad4)") (class "Default")
      (node (ref "J5") (pin "4") (pinfunction "4_4") (pintype "passive+no_connect"))
    )
    (net (code "45") (name "unconnected-(SW2-Pad3)") (class "Default")
      (node (ref "SW2") (pin "3") (pinfunction "3_3") (pintype "passive+no_connect"))
    )
    (net (code "46") (name "unconnected-(U1-CONTROL_VOLTAGE-Pad5)") (class "Default")
      (node (ref "U1") (pin "5") (pinfunction "CONTROL_VOLTAGE_5") (pintype "input+no_connect"))
    )
    (net (code "47") (name "unconnected-(U2-9-Pad11)") (class "Default")
      (node (ref "U2") (pin "11") (pinfunction "9_11") (pintype "output+no_connect"))
    )
    (net (code "48") (name "unconnected-(U2-TC-Pad12)") (class "Default")
      (node (ref "U2") (pin "12") (pinfunction "TC_12") (pintype "output+no_connect"))
    )
  )
)
